# SWI_1_1.net
KiCad netlist of a schematic drawn in EAGLE
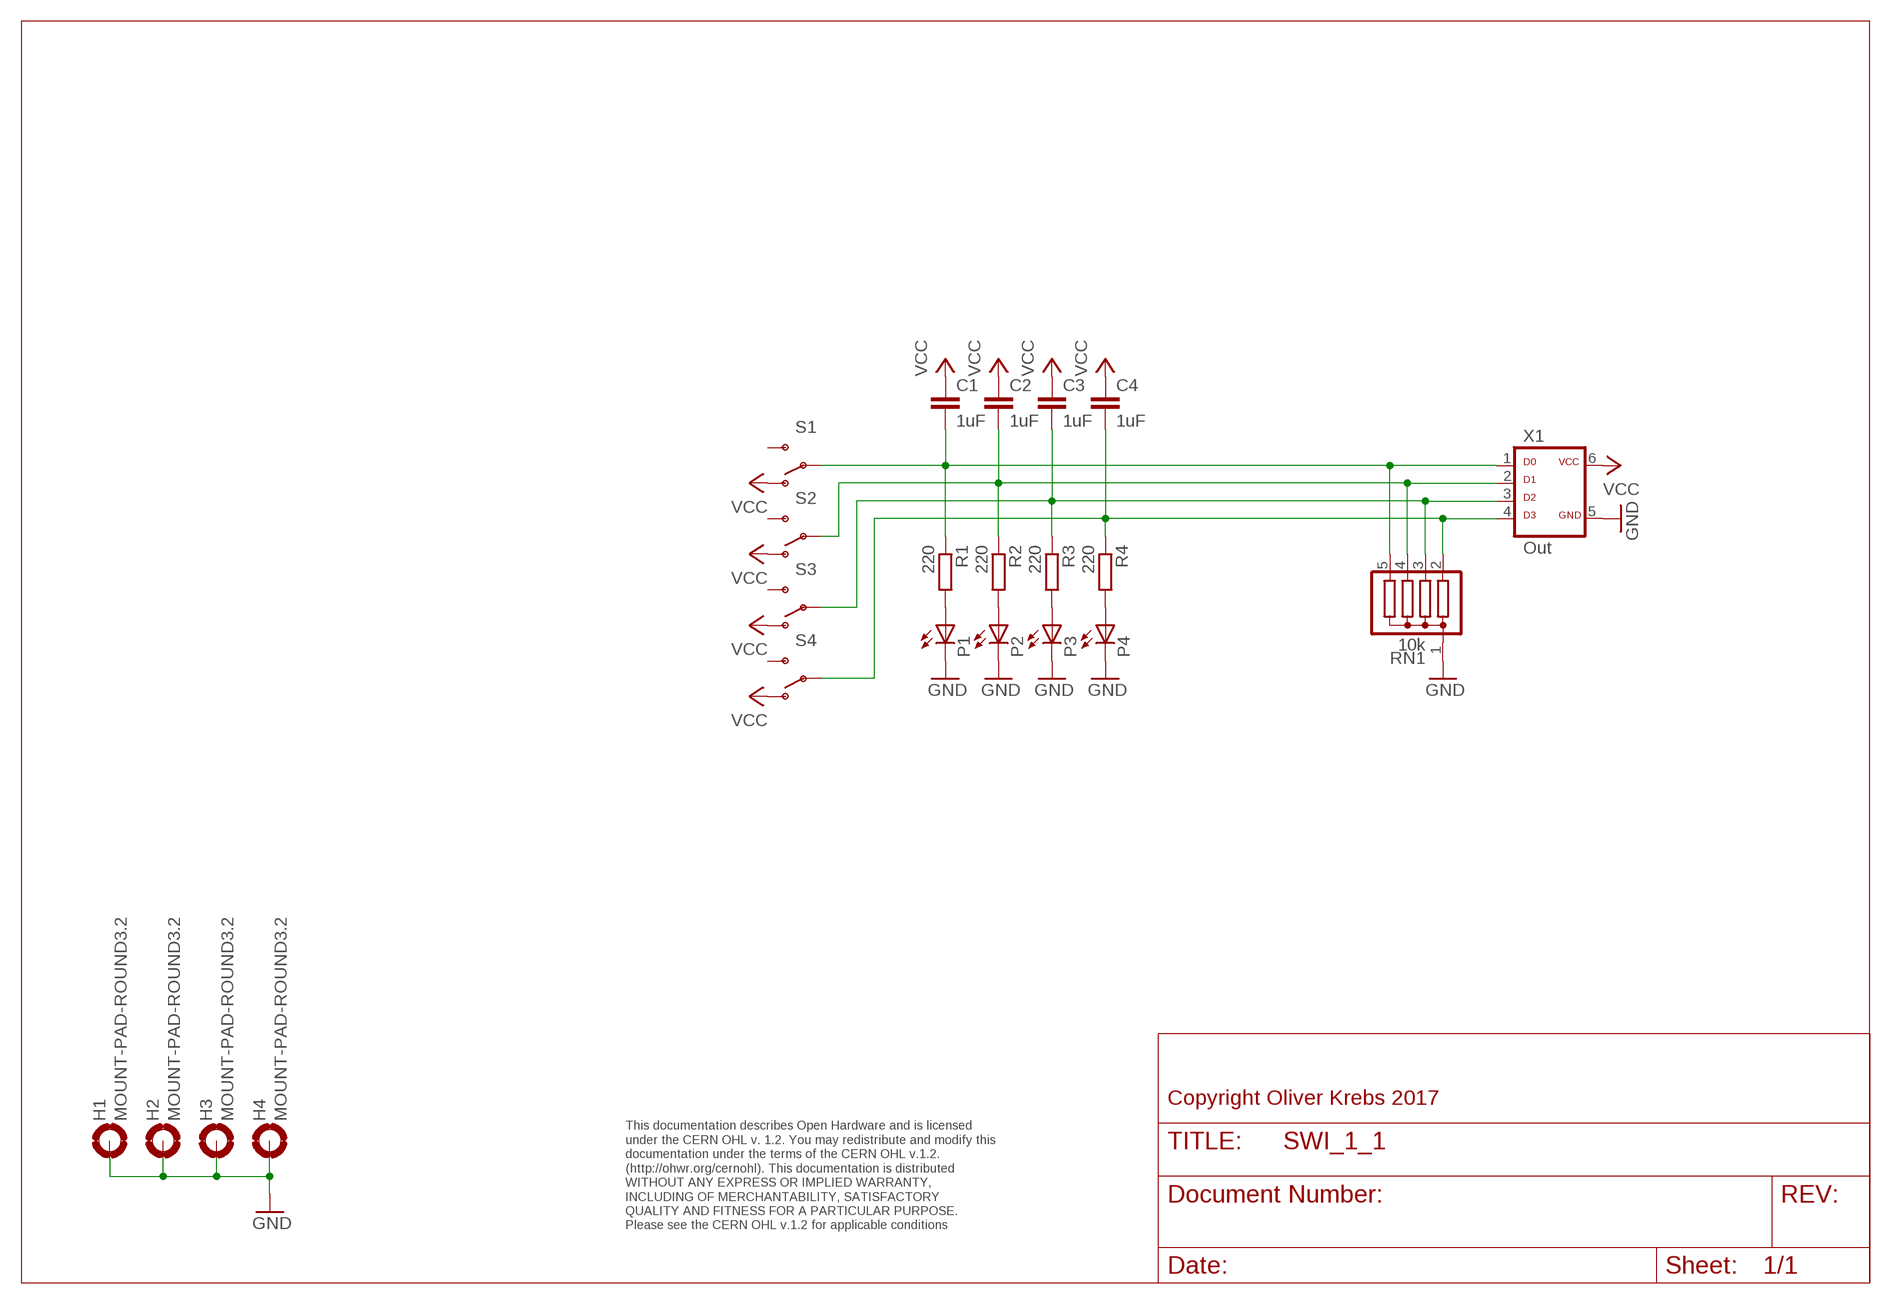
[diagram p0: schematic, sheet 1]

(export (version "E")
  (design (tool "Eeschema 10.0.6"))
  (components
    (comp (ref "C1")
      (value "1uF")
      (footprint "eagle-import:C050-025X075")
      (libsource (lib "eagle-import") (part "C-EU050-025X075"))
    )
    (comp (ref "C2")
      (value "1uF")
      (footprint "eagle-import:C050-025X075")
      (libsource (lib "eagle-import") (part "C-EU050-025X075"))
    )
    (comp (ref "C3")
      (value "1uF")
      (footprint "eagle-import:C050-025X075")
      (libsource (lib "eagle-import") (part "C-EU050-025X075"))
    )
    (comp (ref "C4")
      (value "1uF")
      (footprint "eagle-import:C050-025X075")
      (libsource (lib "eagle-import") (part "C-EU050-025X075"))
    )
    (comp (ref "H1")
      (value "MOUNT-PAD-ROUND3.2")
      (footprint "eagle-import:3,2-PAD")
      (libsource (lib "eagle-import") (part "MOUNT-PAD-ROUND3.2"))
    )
    (comp (ref "H2")
      (value "MOUNT-PAD-ROUND3.2")
      (footprint "eagle-import:3,2-PAD")
      (libsource (lib "eagle-import") (part "MOUNT-PAD-ROUND3.2"))
    )
    (comp (ref "H3")
      (value "MOUNT-PAD-ROUND3.2")
      (footprint "eagle-import:3,2-PAD")
      (libsource (lib "eagle-import") (part "MOUNT-PAD-ROUND3.2"))
    )
    (comp (ref "H4")
      (value "MOUNT-PAD-ROUND3.2")
      (footprint "eagle-import:3,2-PAD")
      (libsource (lib "eagle-import") (part "MOUNT-PAD-ROUND3.2"))
    )
    (comp (ref "P1")
      (value "LED3MM")
      (footprint "eagle-import:LED3MM")
      (libsource (lib "eagle-import") (part "LED3MM"))
    )
    (comp (ref "P2")
      (value "LED3MM")
      (footprint "eagle-import:LED3MM")
      (libsource (lib "eagle-import") (part "LED3MM"))
    )
    (comp (ref "P3")
      (value "LED3MM")
      (footprint "eagle-import:LED3MM")
      (libsource (lib "eagle-import") (part "LED3MM"))
    )
    (comp (ref "P4")
      (value "LED3MM")
      (footprint "eagle-import:LED3MM")
      (libsource (lib "eagle-import") (part "LED3MM"))
    )
    (comp (ref "R1")
      (value "220")
      (footprint "eagle-import:0207_10")
      (libsource (lib "eagle-import") (part "R-EU_0207/10"))
    )
    (comp (ref "R2")
      (value "220")
      (footprint "eagle-import:0207_10")
      (libsource (lib "eagle-import") (part "R-EU_0207/10"))
    )
    (comp (ref "R3")
      (value "220")
      (footprint "eagle-import:0207_10")
      (libsource (lib "eagle-import") (part "R-EU_0207/10"))
    )
    (comp (ref "R4")
      (value "220")
      (footprint "eagle-import:0207_10")
      (libsource (lib "eagle-import") (part "R-EU_0207/10"))
    )
    (comp (ref "RN1")
      (value "10k")
      (footprint "eagle-import:SIL5")
      (libsource (lib "eagle-import") (part "G04R"))
    )
    (comp (ref "S1")
      (value "SWITCH-AS500APC")
      (footprint "eagle-import:SWITCH-AS500APC")
      (libsource (lib "eagle-import") (part "SWITCH-AS500APC"))
    )
    (comp (ref "S2")
      (value "SWITCH-AS500APC")
      (footprint "eagle-import:SWITCH-AS500APC")
      (libsource (lib "eagle-import") (part "SWITCH-AS500APC"))
    )
    (comp (ref "S3")
      (value "SWITCH-AS500APC")
      (footprint "eagle-import:SWITCH-AS500APC")
      (libsource (lib "eagle-import") (part "SWITCH-AS500APC"))
    )
    (comp (ref "S4")
      (value "SWITCH-AS500APC")
      (footprint "eagle-import:SWITCH-AS500APC")
      (libsource (lib "eagle-import") (part "SWITCH-AS500APC"))
    )
    (comp (ref "X1")
      (value "Out")
      (footprint "eagle-import:ML-6")
      (libsource (lib "eagle-import") (part "ML6D"))
    )
  )
  (nets
    (net (code "1") (name "GND") (class "Default")
      (node (ref "H1") (pin "B3,2") (pinfunction "MOUNT_B3,2") (pintype "passive"))
      (node (ref "H2") (pin "B3,2") (pinfunction "MOUNT_B3,2") (pintype "passive"))
      (node (ref "H3") (pin "B3,2") (pinfunction "MOUNT_B3,2") (pintype "passive"))
      (node (ref "H4") (pin "B3,2") (pinfunction "MOUNT_B3,2") (pintype "passive"))
      (node (ref "P1") (pin "K") (pinfunction "C_K") (pintype "passive"))
      (node (ref "P2") (pin "K") (pinfunction "C_K") (pintype "passive"))
      (node (ref "P3") (pin "K") (pinfunction "C_K") (pintype "passive"))
      (node (ref "P4") (pin "K") (pinfunction "C_K") (pintype "passive"))
      (node (ref "RN1") (pin "1") (pinfunction "1_1") (pintype "passive"))
      (node (ref "X1") (pin "5") (pinfunction "5_5") (pintype "passive"))
    )
    (net (code "2") (name "Net-(C1-Pad2)") (class "Default")
      (node (ref "C1") (pin "2") (pinfunction "2_2") (pintype "passive"))
      (node (ref "R1") (pin "1") (pinfunction "1_1") (pintype "passive"))
      (node (ref "RN1") (pin "5") (pinfunction "5_5") (pintype "passive"))
      (node (ref "S1") (pin "P") (pinfunction "P_P") (pintype "passive"))
      (node (ref "X1") (pin "1") (pinfunction "1_1") (pintype "passive"))
    )
    (net (code "3") (name "Net-(C2-Pad2)") (class "Default")
      (node (ref "C2") (pin "2") (pinfunction "2_2") (pintype "passive"))
      (node (ref "R2") (pin "1") (pinfunction "1_1") (pintype "passive"))
      (node (ref "RN1") (pin "4") (pinfunction "4_4") (pintype "passive"))
      (node (ref "S2") (pin "P") (pinfunction "P_P") (pintype "passive"))
      (node (ref "X1") (pin "2") (pinfunction "2_2") (pintype "passive"))
    )
    (net (code "4") (name "Net-(C3-Pad2)") (class "Default")
      (node (ref "C3") (pin "2") (pinfunction "2_2") (pintype "passive"))
      (node (ref "R3") (pin "1") (pinfunction "1_1") (pintype "passive"))
      (node (ref "RN1") (pin "3") (pinfunction "3_3") (pintype "passive"))
      (node (ref "S3") (pin "P") (pinfunction "P_P") (pintype "passive"))
      (node (ref "X1") (pin "3") (pinfunction "3_3") (pintype "passive"))
    )
    (net (code "5") (name "Net-(C4-Pad2)") (class "Default")
      (node (ref "C4") (pin "2") (pinfunction "2_2") (pintype "passive"))
      (node (ref "R4") (pin "1") (pinfunction "1_1") (pintype "passive"))
      (node (ref "RN1") (pin "2") (pinfunction "2_2") (pintype "passive"))
      (node (ref "S4") (pin "P") (pinfunction "P_P") (pintype "passive"))
      (node (ref "X1") (pin "4") (pinfunction "4_4") (pintype "passive"))
    )
    (net (code "6") (name "Net-(P1-PadA)") (class "Default")
      (node (ref "P1") (pin "A") (pinfunction "A_A") (pintype "passive"))
      (node (ref "R1") (pin "2") (pinfunction "2_2") (pintype "passive"))
    )
    (net (code "7") (name "Net-(P2-PadA)") (class "Default")
      (node (ref "P2") (pin "A") (pinfunction "A_A") (pintype "passive"))
      (node (ref "R2") (pin "2") (pinfunction "2_2") (pintype "passive"))
    )
    (net (code "8") (name "Net-(P3-PadA)") (class "Default")
      (node (ref "P3") (pin "A") (pinfunction "A_A") (pintype "passive"))
      (node (ref "R3") (pin "2") (pinfunction "2_2") (pintype "passive"))
    )
    (net (code "9") (name "Net-(P4-PadA)") (class "Default")
      (node (ref "P4") (pin "A") (pinfunction "A_A") (pintype "passive"))
      (node (ref "R4") (pin "2") (pinfunction "2_2") (pintype "passive"))
    )
    (net (code "10") (name "VCC") (class "Default")
      (node (ref "C1") (pin "1") (pinfunction "1_1") (pintype "passive"))
      (node (ref "C2") (pin "1") (pinfunction "1_1") (pintype "passive"))
      (node (ref "C3") (pin "1") (pinfunction "1_1") (pintype "passive"))
      (node (ref "C4") (pin "1") (pinfunction "1_1") (pintype "passive"))
      (node (ref "S1") (pin "O") (pinfunction "O_O") (pintype "passive"))
      (node (ref "S2") (pin "O") (pinfunction "O_O") (pintype "passive"))
      (node (ref "S3") (pin "O") (pinfunction "O_O") (pintype "passive"))
      (node (ref "S4") (pin "O") (pinfunction "O_O") (pintype "passive"))
      (node (ref "X1") (pin "6") (pinfunction "6_6") (pintype "passive"))
    )
    (net (code "11") (name "unconnected-(S1-PadS)") (class "Default")
      (node (ref "S1") (pin "S") (pinfunction "S_S") (pintype "passive"))
    )
    (net (code "12") (name "unconnected-(S2-PadS)") (class "Default")
      (node (ref "S2") (pin "S") (pinfunction "S_S") (pintype "passive"))
    )
    (net (code "13") (name "unconnected-(S3-PadS)") (class "Default")
      (node (ref "S3") (pin "S") (pinfunction "S_S") (pintype "passive"))
    )
    (net (code "14") (name "unconnected-(S4-PadS)") (class "Default")
      (node (ref "S4") (pin "S") (pinfunction "S_S") (pintype "passive"))
    )
  )
)
